# MOS_stage.net
KiCad netlist of a schematic drawn in EAGLE
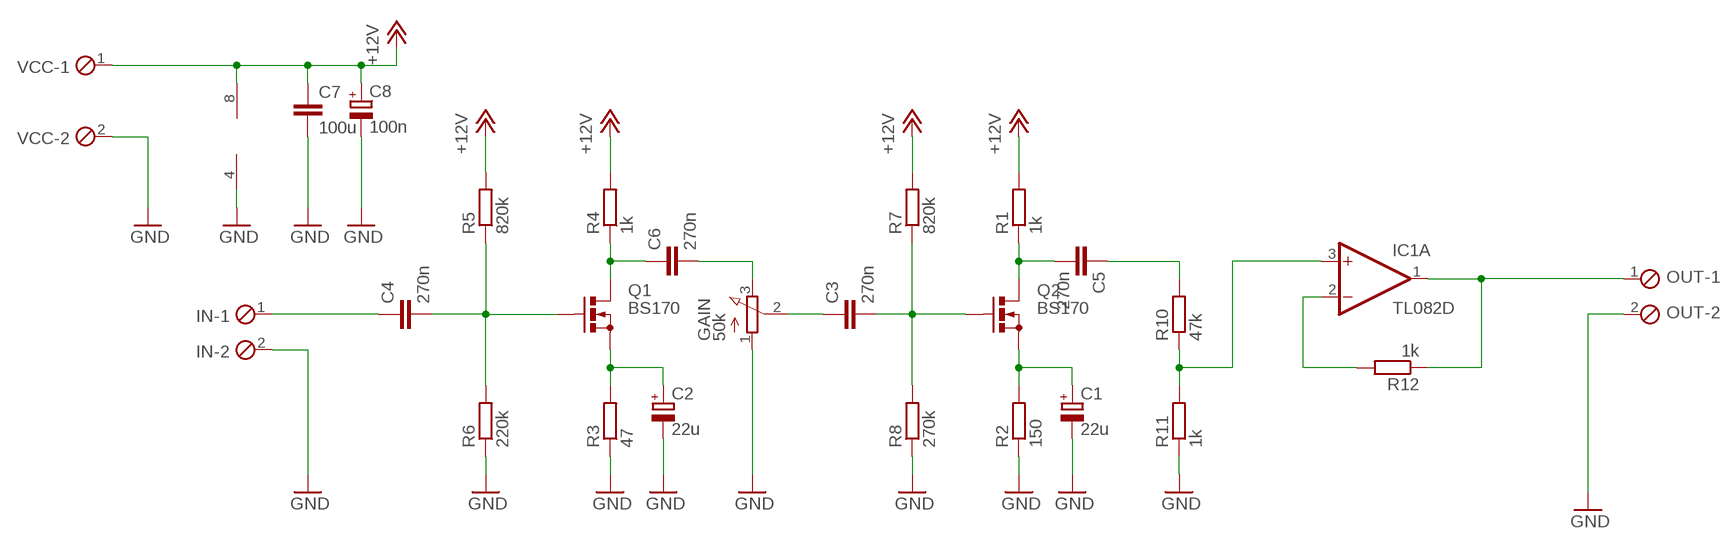
[diagram p0: schematic, sheet 1]

(export (version "E")
  (design (tool "Eeschema 10.0.6"))
  (components
    (comp (ref "C1")
      (value "22u")
      (footprint "eagle-import:E2,5-5")
      (libsource (lib "eagle-import") (part "CPOL-EUE2.5-5"))
    )
    (comp (ref "C2")
      (value "22u")
      (footprint "eagle-import:E2,5-5")
      (libsource (lib "eagle-import") (part "CPOL-EUE2.5-5"))
    )
    (comp (ref "C3")
      (value "270n")
      (footprint "eagle-import:C1206")
      (libsource (lib "eagle-import") (part "C-EUC1206"))
    )
    (comp (ref "C4")
      (value "270n")
      (footprint "eagle-import:C1206")
      (libsource (lib "eagle-import") (part "C-EUC1206"))
    )
    (comp (ref "C5")
      (value "270n")
      (footprint "eagle-import:C1206")
      (libsource (lib "eagle-import") (part "C-EUC1206"))
    )
    (comp (ref "C6")
      (value "270n")
      (footprint "eagle-import:C1206")
      (libsource (lib "eagle-import") (part "C-EUC1206"))
    )
    (comp (ref "C7")
      (value "100u")
      (footprint "eagle-import:C1206")
      (libsource (lib "eagle-import") (part "C-EUC1206"))
    )
    (comp (ref "C8")
      (value "100n")
      (footprint "eagle-import:E2,5-5")
      (libsource (lib "eagle-import") (part "CPOL-EUE2.5-5"))
    )
    (comp (ref "GAIN")
      (value "50k")
      (footprint "eagle-import:3RP_1610N")
      (libsource (lib "eagle-import") (part "3RP/1610N"))
    )
    (comp (ref "IC1")
      (value "TL082D")
      (footprint "eagle-import:SO08")
      (libsource (lib "eagle-import") (part "TL082D"))
    )
    (comp (ref "IN")
      (value "MPT2")
      (footprint "eagle-import:2POL254")
      (libsource (lib "eagle-import") (part "MPT2"))
    )
    (comp (ref "OUT")
      (value "MPT2")
      (footprint "eagle-import:2POL254")
      (libsource (lib "eagle-import") (part "MPT2"))
    )
    (comp (ref "Q1")
      (value "BS170")
      (footprint "eagle-import:SOT54E")
      (libsource (lib "eagle-import") (part "BS170"))
    )
    (comp (ref "Q2")
      (value "BS170")
      (footprint "eagle-import:SOT54E")
      (libsource (lib "eagle-import") (part "BS170"))
    )
    (comp (ref "R1")
      (value "1k")
      (footprint "eagle-import:R0805")
      (libsource (lib "eagle-import") (part "R-EU_R0805"))
    )
    (comp (ref "R2")
      (value "150")
      (footprint "eagle-import:R0805")
      (libsource (lib "eagle-import") (part "R-EU_R0805"))
    )
    (comp (ref "R3")
      (value "47")
      (footprint "eagle-import:R0805")
      (libsource (lib "eagle-import") (part "R-EU_R0805"))
    )
    (comp (ref "R4")
      (value "1k")
      (footprint "eagle-import:R0805")
      (libsource (lib "eagle-import") (part "R-EU_R0805"))
    )
    (comp (ref "R5")
      (value "820k")
      (footprint "eagle-import:R0805")
      (libsource (lib "eagle-import") (part "R-EU_R0805"))
    )
    (comp (ref "R6")
      (value "220k")
      (footprint "eagle-import:R0805")
      (libsource (lib "eagle-import") (part "R-EU_R0805"))
    )
    (comp (ref "R7")
      (value "820k")
      (footprint "eagle-import:R0805")
      (libsource (lib "eagle-import") (part "R-EU_R0805"))
    )
    (comp (ref "R8")
      (value "270k")
      (footprint "eagle-import:R0805")
      (libsource (lib "eagle-import") (part "R-EU_R0805"))
    )
    (comp (ref "R10")
      (value "47k")
      (footprint "eagle-import:R0805")
      (libsource (lib "eagle-import") (part "R-EU_R0805"))
    )
    (comp (ref "R11")
      (value "1k")
      (footprint "eagle-import:R0805")
      (libsource (lib "eagle-import") (part "R-EU_R0805"))
    )
    (comp (ref "R12")
      (value "1k")
      (footprint "eagle-import:R0805")
      (libsource (lib "eagle-import") (part "R-EU_R0805"))
    )
    (comp (ref "VCC")
      (value "MPT2")
      (footprint "eagle-import:2POL254")
      (libsource (lib "eagle-import") (part "MPT2"))
    )
  )
  (nets
    (net (code "1") (name "+12V") (class "Default")
      (node (ref "C7") (pin "1") (pinfunction "1_1") (pintype "passive"))
      (node (ref "C8") (pin "+") (pinfunction "+_+") (pintype "passive"))
      (node (ref "IC1") (pin "8") (pinfunction "V+_8") (pintype "power_in"))
      (node (ref "R1") (pin "2") (pinfunction "2_2") (pintype "passive"))
      (node (ref "R4") (pin "2") (pinfunction "2_2") (pintype "passive"))
      (node (ref "R5") (pin "2") (pinfunction "2_2") (pintype "passive"))
      (node (ref "R7") (pin "2") (pinfunction "2_2") (pintype "passive"))
      (node (ref "VCC") (pin "1") (pinfunction "1_1") (pintype "passive"))
    )
    (net (code "2") (name "GND") (class "Default")
      (node (ref "C1") (pin "-") (pinfunction "-_-") (pintype "passive"))
      (node (ref "C2") (pin "-") (pinfunction "-_-") (pintype "passive"))
      (node (ref "C7") (pin "2") (pinfunction "2_2") (pintype "passive"))
      (node (ref "C8") (pin "-") (pinfunction "-_-") (pintype "passive"))
      (node (ref "GAIN") (pin "1") (pinfunction "A_1") (pintype "passive"))
      (node (ref "IC1") (pin "4") (pinfunction "V-_4") (pintype "power_in"))
      (node (ref "IN") (pin "2") (pinfunction "1_2") (pintype "passive"))
      (node (ref "OUT") (pin "2") (pinfunction "1_2") (pintype "passive"))
      (node (ref "R11") (pin "1") (pinfunction "1_1") (pintype "passive"))
      (node (ref "R2") (pin "1") (pinfunction "1_1") (pintype "passive"))
      (node (ref "R3") (pin "1") (pinfunction "1_1") (pintype "passive"))
      (node (ref "R6") (pin "1") (pinfunction "1_1") (pintype "passive"))
      (node (ref "R8") (pin "1") (pinfunction "1_1") (pintype "passive"))
      (node (ref "VCC") (pin "2") (pinfunction "1_2") (pintype "passive"))
    )
    (net (code "3") (name "Net-(C1-Pad+)") (class "Default")
      (node (ref "C1") (pin "+") (pinfunction "+_+") (pintype "passive"))
      (node (ref "Q2") (pin "S") (pinfunction "S_S") (pintype "passive"))
      (node (ref "R2") (pin "2") (pinfunction "2_2") (pintype "passive"))
    )
    (net (code "4") (name "Net-(C2-Pad+)") (class "Default")
      (node (ref "C2") (pin "+") (pinfunction "+_+") (pintype "passive"))
      (node (ref "Q1") (pin "S") (pinfunction "S_S") (pintype "passive"))
      (node (ref "R3") (pin "2") (pinfunction "2_2") (pintype "passive"))
    )
    (net (code "5") (name "Net-(C3-Pad2)") (class "Default")
      (node (ref "C3") (pin "2") (pinfunction "2_2") (pintype "passive"))
      (node (ref "Q2") (pin "G") (pinfunction "G_G") (pintype "passive"))
      (node (ref "R7") (pin "1") (pinfunction "1_1") (pintype "passive"))
      (node (ref "R8") (pin "2") (pinfunction "2_2") (pintype "passive"))
    )
    (net (code "6") (name "Net-(C4-Pad1)") (class "Default")
      (node (ref "C4") (pin "1") (pinfunction "1_1") (pintype "passive"))
      (node (ref "IN") (pin "1") (pinfunction "1_1") (pintype "passive"))
    )
    (net (code "7") (name "Net-(C4-Pad2)") (class "Default")
      (node (ref "C4") (pin "2") (pinfunction "2_2") (pintype "passive"))
      (node (ref "Q1") (pin "G") (pinfunction "G_G") (pintype "passive"))
      (node (ref "R5") (pin "1") (pinfunction "1_1") (pintype "passive"))
      (node (ref "R6") (pin "2") (pinfunction "2_2") (pintype "passive"))
    )
    (net (code "8") (name "Net-(C5-Pad1)") (class "Default")
      (node (ref "C5") (pin "1") (pinfunction "1_1") (pintype "passive"))
      (node (ref "R10") (pin "2") (pinfunction "2_2") (pintype "passive"))
    )
    (net (code "9") (name "Net-(C5-Pad2)") (class "Default")
      (node (ref "C5") (pin "2") (pinfunction "2_2") (pintype "passive"))
      (node (ref "Q2") (pin "D") (pinfunction "D_D") (pintype "passive"))
      (node (ref "R1") (pin "1") (pinfunction "1_1") (pintype "passive"))
    )
    (net (code "10") (name "Net-(C6-Pad1)") (class "Default")
      (node (ref "C6") (pin "1") (pinfunction "1_1") (pintype "passive"))
      (node (ref "Q1") (pin "D") (pinfunction "D_D") (pintype "passive"))
      (node (ref "R4") (pin "1") (pinfunction "1_1") (pintype "passive"))
    )
    (net (code "11") (name "Net-(GAIN-E)") (class "Default")
      (node (ref "C6") (pin "2") (pinfunction "2_2") (pintype "passive"))
      (node (ref "GAIN") (pin "3") (pinfunction "E_3") (pintype "passive"))
    )
    (net (code "12") (name "Net-(GAIN-S)") (class "Default")
      (node (ref "C3") (pin "1") (pinfunction "1_1") (pintype "passive"))
      (node (ref "GAIN") (pin "2") (pinfunction "S_2") (pintype "passive"))
    )
    (net (code "13") (name "Net-(IC1A-+IN)") (class "Default")
      (node (ref "IC1") (pin "3") (pinfunction "+IN_3") (pintype "input"))
      (node (ref "R10") (pin "1") (pinfunction "1_1") (pintype "passive"))
      (node (ref "R11") (pin "2") (pinfunction "2_2") (pintype "passive"))
    )
    (net (code "14") (name "Net-(IC1A--IN)") (class "Default")
      (node (ref "IC1") (pin "2") (pinfunction "-IN_2") (pintype "input"))
      (node (ref "R12") (pin "2") (pinfunction "2_2") (pintype "passive"))
    )
    (net (code "15") (name "Net-(IC1A-OUT)") (class "Default")
      (node (ref "IC1") (pin "1") (pinfunction "OUT_1") (pintype "output"))
      (node (ref "OUT") (pin "1") (pinfunction "1_1") (pintype "passive"))
      (node (ref "R12") (pin "1") (pinfunction "1_1") (pintype "passive"))
    )
  )
)
